# Boost-Shield.net
KiCad netlist of a schematic drawn in Altium Designer
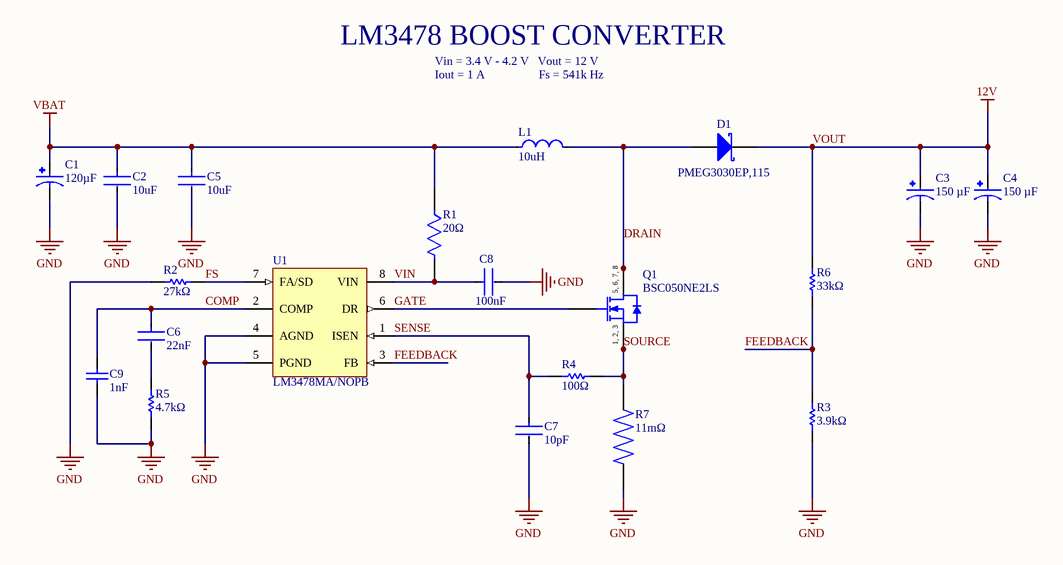
[diagram p0: Boost-Shield.SchDoc]

(export (version "E")
  (design (tool "Eeschema 10.0.6"))
  (components
    (comp (ref "C1")
      (value "120µF")
      (footprint "CAP_EEFCX0J121R")
      (description "120µF 6.3V Aluminum - Polymer Capacitors 2917 (7343 Metric) 15mOhm 2000 Hrs @ 105°C  EEFCX0J121R")
      (libsource (lib "Boost-Shield") (part "EEFCX0J121R"))
    )
    (comp (ref "C2")
      (value "10uF")
      (footprint "FP-C0805C-DG-MFG")
      (description "CAP CER 10UF 10V X5R 0805")
      (fields (field (name "TOLERANCE") "10%") (field (name "MANUFACTURER PART NUMBER") "C0805C106K8PACTU"))
      (libsource (lib "Altium Content Vault") (part "11868f565c42a9108669ba33697ecf6"))
    )
    (comp (ref "C3")
      (value "150 µF")
      (footprint "CAP_16TDC150MYF")
      (description "150 µF Molded Tantalum Polymer Capacitor 16 V 2917 (7343 Metric) 50mOhm @ 100kHz")
      (libsource (lib "Boost-Shield") (part "16TDC150MYF"))
    )
    (comp (ref "C4")
      (value "150 µF")
      (footprint "CAP_16TDC150MYF")
      (description "150 µF Molded Tantalum Polymer Capacitor 16 V 2917 (7343 Metric) 50mOhm @ 100kHz")
      (libsource (lib "Boost-Shield") (part "16TDC150MYF"))
    )
    (comp (ref "C5")
      (value "10uF")
      (footprint "FP-C0805C-DG-MFG")
      (description "CAP CER 10UF 10V X5R 0805")
      (fields (field (name "TOLERANCE") "10%") (field (name "MANUFACTURER PART NUMBER") "C0805C106K8PACTU"))
      (libsource (lib "Altium Content Vault") (part "11868f565c42a9108669ba33697ecf6"))
    )
    (comp (ref "C6")
      (value "22nF")
      (footprint "FP-CGA4J-MFG")
      (description "Cap Ceramic 22nF 50V C0G 5% Pad SMD 0805 +125°C Automotive T/R CGJ4J2C0G1H223J125AA")
      (fields (field (name "TOLERANCE") "5%"))
      (libsource (lib "Altium Content Vault") (part "b4654b650e69147ec39a6b967a45e02"))
    )
    (comp (ref "C7")
      (value "10pF")
      (footprint "FP-C0805C-DN-MFG")
      (description "CAP CER 10PF 16V 20% NP0 0805")
      (fields
        (field (name "MANUFACTURER PART NUMBER") "C0805C100M4GACTU")
        (field (name "OCTOPART") "https://octopart.com/c0805c100m4gactu-kemet-16430157")
      )
      (libsource (lib "Altium Content Vault") (part "b4654b650e69147ec39a6b967a45e02"))
    )
    (comp (ref "C8")
      (value "100nF")
      (footprint "FP-CC0805-0_85-MFG")
      (description "CAP CER 0.1UF 16V X7R 0805")
      (fields
        (field (name "MANUFACTURER PART NUMBER") "CC0805KRX7R7BB104")
        (field (name "MANUFACTURER") "Yageo")
      )
      (libsource (lib "Altium Content Vault") (part "11868f565c42a9108669ba33697ecf6"))
    )
    (comp (ref "C9")
      (value "1nF")
      (footprint "CAPC2013X140X50NL20T25")
      (description "08051A102JAT2A")
      (fields (field (name "MANUFACTURER") "AVX Interconnect / Elco"))
      (libsource (lib "Altium Content Vault") (part "CAP"))
    )
    (comp (ref "D1")
      (value "PMEG3030EP,115")
      (footprint "NXP-SOD128_V")
      (description "Schottky Barrier Rectifier, 3 A, 30 V, -55 to 150 degC, 2-Pin SOD128, RoHS, Tape and Reel")
      (fields (field (name "MANUFACTURER") "NXP Semiconductors"))
      (libsource (lib "Altium Content Vault") (part "DSKY-AK-2"))
    )
    (comp (ref "L1")
      (value "10uH")
      (footprint "FP-IHLP-3232DZ-FP_2_413x5-MFG")
      (description "FIXED IND 10UH 5.2A 59.9 MOHM")
      (fields (field (name "TOLERANCE") "20%"))
      (libsource (lib "Altium Content Vault") (part "725321dda6339637d4d059423bc1c3c"))
    )
    (comp (ref "Q1")
      (value "BSC050NE2LS")
      (footprint "INF-PG-TDSON-8-1_V")
      (description "N-Channel OptiMOS Power-MOSFET, 25 V VDS, 58 A ID, -55 to 150 degC, PG-TDSON-8-1, Reel, Green")
      (fields (field (name "MANUFACTURER") "Infineon"))
      (libsource (lib "Altium Content Vault") (part "INF-NEMOS-SSSGDDDD-8"))
    )
    (comp (ref "R1")
      (value "20Ω")
      (footprint "FP-CRCW0805-e3-IPC_C")
      (description "RES Thick Film, 20Ω, 1%, 0.125W, 100ppm/°C, 0805")
      (fields (field (name "TOLERANCE") "1%"))
      (libsource (lib "Altium Content Vault") (part "1029c3af85768c4190bb7ad29bc67b5"))
    )
    (comp (ref "R2")
      (value "27kΩ")
      (footprint "RESC2013X50X30ML20T20")
      (description "CRCW080527K0FKEA")
      (fields (field (name "MANUFACTURER") "Vishay Dale"))
      (libsource (lib "Altium Content Vault") (part "RES"))
    )
    (comp (ref "R3")
      (value "3.9kΩ")
      (footprint "RESC2013X50X30LL20T20")
      (description "CRCW08053K90FKEA")
      (fields (field (name "MANUFACTURER") "Vishay Dale"))
      (libsource (lib "Altium Content Vault") (part "RES"))
    )
    (comp (ref "R4")
      (value "100Ω")
      (footprint "RESC2013X50X30ML20T20")
      (description "CRCW0805100RJNEA")
      (fields (field (name "MANUFACTURER") "Vishay Dale"))
      (libsource (lib "Altium Content Vault") (part "RES"))
    )
    (comp (ref "R5")
      (value "4.7kΩ")
      (footprint "RESC2013X70X40NL20T20")
      (description "Chip Resistor, 4.7 KOhm, +/- 1%, 0.125 W, -55 to 155 degC, 0805 (2012 Metric), RoHS, Tape and Reel")
      (fields (field (name "MANUFACTURER") "Panasonic"))
      (libsource (lib "Altium Content Vault") (part "RES-2"))
    )
    (comp (ref "R6")
      (value "33kΩ")
      (footprint "RESC2013X50X30LL20T20")
      (description "CRCW080533K0JNEA")
      (fields (field (name "MANUFACTURER") "Vishay Dale"))
      (libsource (lib "Altium Content Vault") (part "RES"))
    )
    (comp (ref "R7")
      (value "11mΩ")
      (footprint "RESC3115X65N")
      (description "11 mOhms ±1% 0.5W, 1/2W Chip Resistor 1206 (3216 Metric) Current Sense Thick Film")
      (libsource (lib "Boost-Shield") (part "RLP73V2BR011FTDF"))
    )
    (comp (ref "U1")
      (value "LM3478MA/NOPB")
      (footprint "D0008A_L")
      (fields (field (name "MANUFACTURER") "Texas Instruments"))
      (libsource (lib "Altium Content Vault") (part "PM-SWREG-LM3478-8"))
    )
  )
  (nets
    (net (code "1") (name "/COMP") (class "Default")
      (node (ref "C6") (pin "1") (pinfunction "1_1") (pintype "passive"))
      (node (ref "C9") (pin "2") (pinfunction "2_2") (pintype "passive"))
      (node (ref "U1") (pin "2") (pinfunction "COMP_2") (pintype "passive"))
    )
    (net (code "2") (name "/DRAIN") (class "Default")
      (node (ref "D1") (pin "1") (pinfunction "A_1") (pintype "passive"))
      (node (ref "L1") (pin "2") (pinfunction "2_2") (pintype "passive"))
      (node (ref "Q1") (pin "5") (pinfunction "DRAIN_5") (pintype "passive"))
      (node (ref "Q1") (pin "6") (pinfunction "DRAIN_6") (pintype "passive"))
      (node (ref "Q1") (pin "7") (pinfunction "DRAIN_7") (pintype "passive"))
      (node (ref "Q1") (pin "8") (pinfunction "DRAIN_8") (pintype "passive"))
    )
    (net (code "3") (name "/FEEDBACK") (class "Default")
      (node (ref "R3") (pin "2") (pinfunction "2_2") (pintype "passive"))
      (node (ref "R6") (pin "1") (pinfunction "1_1") (pintype "passive"))
      (node (ref "U1") (pin "3") (pinfunction "FB_3") (pintype "input"))
    )
    (net (code "4") (name "/FS") (class "Default")
      (node (ref "R2") (pin "2") (pinfunction "2_2") (pintype "passive"))
      (node (ref "U1") (pin "7") (pinfunction "FA/SD_7") (pintype "input"))
    )
    (net (code "5") (name "/GATE") (class "Default")
      (node (ref "Q1") (pin "4") (pinfunction "GATE_4") (pintype "passive"))
      (node (ref "U1") (pin "6") (pinfunction "DR_6") (pintype "output"))
    )
    (net (code "6") (name "/SENSE") (class "Default")
      (node (ref "C7") (pin "1") (pinfunction "1_1") (pintype "passive"))
      (node (ref "R4") (pin "1") (pinfunction "1_1") (pintype "passive"))
      (node (ref "U1") (pin "1") (pinfunction "ISEN_1") (pintype "input"))
    )
    (net (code "7") (name "/SOURCE") (class "Default")
      (node (ref "Q1") (pin "1") (pinfunction "SOURCE_1") (pintype "passive"))
      (node (ref "Q1") (pin "2") (pinfunction "SOURCE_2") (pintype "passive"))
      (node (ref "Q1") (pin "3") (pinfunction "SOURCE_3") (pintype "passive"))
      (node (ref "R4") (pin "2") (pinfunction "2_2") (pintype "passive"))
      (node (ref "R7") (pin "2") (pinfunction "2_2") (pintype "passive"))
    )
    (net (code "8") (name "/VIN") (class "Default")
      (node (ref "C8") (pin "1") (pinfunction "1_1") (pintype "passive"))
      (node (ref "R1") (pin "2") (pinfunction "2_2") (pintype "passive"))
      (node (ref "U1") (pin "8") (pinfunction "VIN_8") (pintype "power_in"))
    )
    (net (code "9") (name "12V") (class "Default")
      (node (ref "C3") (pin "1") (pinfunction "1_1") (pintype "passive"))
      (node (ref "C4") (pin "1") (pinfunction "1_1") (pintype "passive"))
      (node (ref "D1") (pin "2") (pinfunction "K_2") (pintype "passive"))
      (node (ref "R6") (pin "2") (pinfunction "2_2") (pintype "passive"))
    )
    (net (code "10") (name "GND") (class "Default")
      (node (ref "C1") (pin "2") (pinfunction "2_2") (pintype "passive"))
      (node (ref "C2") (pin "2") (pinfunction "2_2") (pintype "passive"))
      (node (ref "C3") (pin "2") (pinfunction "2_2") (pintype "passive"))
      (node (ref "C4") (pin "2") (pinfunction "2_2") (pintype "passive"))
      (node (ref "C5") (pin "2") (pinfunction "2_2") (pintype "passive"))
      (node (ref "C7") (pin "2") (pinfunction "2_2") (pintype "passive"))
      (node (ref "C8") (pin "2") (pinfunction "2_2") (pintype "passive"))
      (node (ref "C9") (pin "1") (pinfunction "1_1") (pintype "passive"))
      (node (ref "R2") (pin "1") (pinfunction "1_1") (pintype "passive"))
      (node (ref "R3") (pin "1") (pinfunction "1_1") (pintype "passive"))
      (node (ref "R5") (pin "1") (pinfunction "1_1") (pintype "passive"))
      (node (ref "R7") (pin "1") (pinfunction "1_1") (pintype "passive"))
      (node (ref "U1") (pin "4") (pinfunction "AGND_4") (pintype "power_in"))
      (node (ref "U1") (pin "5") (pinfunction "PGND_5") (pintype "power_in"))
    )
    (net (code "11") (name "Net-(C6-Pad2)") (class "Default")
      (node (ref "C6") (pin "2") (pinfunction "2_2") (pintype "passive"))
      (node (ref "R5") (pin "2") (pinfunction "2_2") (pintype "passive"))
    )
    (net (code "12") (name "VBAT") (class "Default")
      (node (ref "C1") (pin "1") (pinfunction "1_1") (pintype "passive"))
      (node (ref "C2") (pin "1") (pinfunction "1_1") (pintype "passive"))
      (node (ref "C5") (pin "1") (pinfunction "1_1") (pintype "passive"))
      (node (ref "L1") (pin "1") (pinfunction "1_1") (pintype "passive"))
      (node (ref "R1") (pin "1") (pinfunction "1_1") (pintype "passive"))
    )
  )
)
